# 0805_Breakout_Board.net
KiCad netlist of a schematic drawn in EAGLE
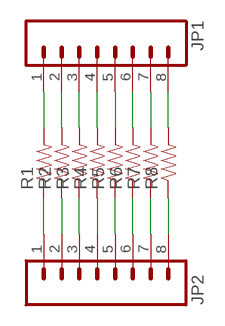
[diagram p0: schematic, sheet 1]

(export (version "E")
  (design (tool "Eeschema 10.0.6"))
  (components
    (comp (ref "JP1")
      (value "M08")
      (footprint "eagle-import:1X08")
      (libsource (lib "eagle-import") (part "M08"))
    )
    (comp (ref "JP2")
      (value "M08")
      (footprint "eagle-import:1X08")
      (libsource (lib "eagle-import") (part "M08"))
    )
    (comp (ref "R1")
      (value "RESISTOR0805-RES")
      (footprint "eagle-import:0805")
      (libsource (lib "eagle-import") (part "RESISTOR0805-RES"))
    )
    (comp (ref "R2")
      (value "RESISTOR0805-RES")
      (footprint "eagle-import:0805")
      (libsource (lib "eagle-import") (part "RESISTOR0805-RES"))
    )
    (comp (ref "R3")
      (value "RESISTOR0805-RES")
      (footprint "eagle-import:0805")
      (libsource (lib "eagle-import") (part "RESISTOR0805-RES"))
    )
    (comp (ref "R4")
      (value "RESISTOR0805-RES")
      (footprint "eagle-import:0805")
      (libsource (lib "eagle-import") (part "RESISTOR0805-RES"))
    )
    (comp (ref "R5")
      (value "RESISTOR0805-RES")
      (footprint "eagle-import:0805")
      (libsource (lib "eagle-import") (part "RESISTOR0805-RES"))
    )
    (comp (ref "R6")
      (value "RESISTOR0805-RES")
      (footprint "eagle-import:0805")
      (libsource (lib "eagle-import") (part "RESISTOR0805-RES"))
    )
    (comp (ref "R7")
      (value "RESISTOR0805-RES")
      (footprint "eagle-import:0805")
      (libsource (lib "eagle-import") (part "RESISTOR0805-RES"))
    )
    (comp (ref "R8")
      (value "RESISTOR0805-RES")
      (footprint "eagle-import:0805")
      (libsource (lib "eagle-import") (part "RESISTOR0805-RES"))
    )
  )
  (nets
    (net (code "1") (name "Net-(JP1-Pad1)") (class "Default")
      (node (ref "JP1") (pin "1") (pinfunction "1_1") (pintype "passive"))
      (node (ref "R1") (pin "2") (pinfunction "2_2") (pintype "passive"))
    )
    (net (code "2") (name "Net-(JP1-Pad2)") (class "Default")
      (node (ref "JP1") (pin "2") (pinfunction "2_2") (pintype "passive"))
      (node (ref "R2") (pin "2") (pinfunction "2_2") (pintype "passive"))
    )
    (net (code "3") (name "Net-(JP1-Pad3)") (class "Default")
      (node (ref "JP1") (pin "3") (pinfunction "3_3") (pintype "passive"))
      (node (ref "R3") (pin "2") (pinfunction "2_2") (pintype "passive"))
    )
    (net (code "4") (name "Net-(JP1-Pad4)") (class "Default")
      (node (ref "JP1") (pin "4") (pinfunction "4_4") (pintype "passive"))
      (node (ref "R4") (pin "2") (pinfunction "2_2") (pintype "passive"))
    )
    (net (code "5") (name "Net-(JP1-Pad5)") (class "Default")
      (node (ref "JP1") (pin "5") (pinfunction "5_5") (pintype "passive"))
      (node (ref "R5") (pin "2") (pinfunction "2_2") (pintype "passive"))
    )
    (net (code "6") (name "Net-(JP1-Pad6)") (class "Default")
      (node (ref "JP1") (pin "6") (pinfunction "6_6") (pintype "passive"))
      (node (ref "R6") (pin "2") (pinfunction "2_2") (pintype "passive"))
    )
    (net (code "7") (name "Net-(JP1-Pad7)") (class "Default")
      (node (ref "JP1") (pin "7") (pinfunction "7_7") (pintype "passive"))
      (node (ref "R7") (pin "2") (pinfunction "2_2") (pintype "passive"))
    )
    (net (code "8") (name "Net-(JP1-Pad8)") (class "Default")
      (node (ref "JP1") (pin "8") (pinfunction "8_8") (pintype "passive"))
      (node (ref "R8") (pin "2") (pinfunction "2_2") (pintype "passive"))
    )
    (net (code "9") (name "Net-(JP2-Pad1)") (class "Default")
      (node (ref "JP2") (pin "1") (pinfunction "1_1") (pintype "passive"))
      (node (ref "R1") (pin "1") (pinfunction "1_1") (pintype "passive"))
    )
    (net (code "10") (name "Net-(JP2-Pad2)") (class "Default")
      (node (ref "JP2") (pin "2") (pinfunction "2_2") (pintype "passive"))
      (node (ref "R2") (pin "1") (pinfunction "1_1") (pintype "passive"))
    )
    (net (code "11") (name "Net-(JP2-Pad3)") (class "Default")
      (node (ref "JP2") (pin "3") (pinfunction "3_3") (pintype "passive"))
      (node (ref "R3") (pin "1") (pinfunction "1_1") (pintype "passive"))
    )
    (net (code "12") (name "Net-(JP2-Pad4)") (class "Default")
      (node (ref "JP2") (pin "4") (pinfunction "4_4") (pintype "passive"))
      (node (ref "R4") (pin "1") (pinfunction "1_1") (pintype "passive"))
    )
    (net (code "13") (name "Net-(JP2-Pad5)") (class "Default")
      (node (ref "JP2") (pin "5") (pinfunction "5_5") (pintype "passive"))
      (node (ref "R5") (pin "1") (pinfunction "1_1") (pintype "passive"))
    )
    (net (code "14") (name "Net-(JP2-Pad6)") (class "Default")
      (node (ref "JP2") (pin "6") (pinfunction "6_6") (pintype "passive"))
      (node (ref "R6") (pin "1") (pinfunction "1_1") (pintype "passive"))
    )
    (net (code "15") (name "Net-(JP2-Pad7)") (class "Default")
      (node (ref "JP2") (pin "7") (pinfunction "7_7") (pintype "passive"))
      (node (ref "R7") (pin "1") (pinfunction "1_1") (pintype "passive"))
    )
    (net (code "16") (name "Net-(JP2-Pad8)") (class "Default")
      (node (ref "JP2") (pin "8") (pinfunction "8_8") (pintype "passive"))
      (node (ref "R8") (pin "1") (pinfunction "1_1") (pintype "passive"))
    )
  )
)
